# EE209_Schematic_SMT.net
KiCad netlist of a schematic drawn in Altium Designer
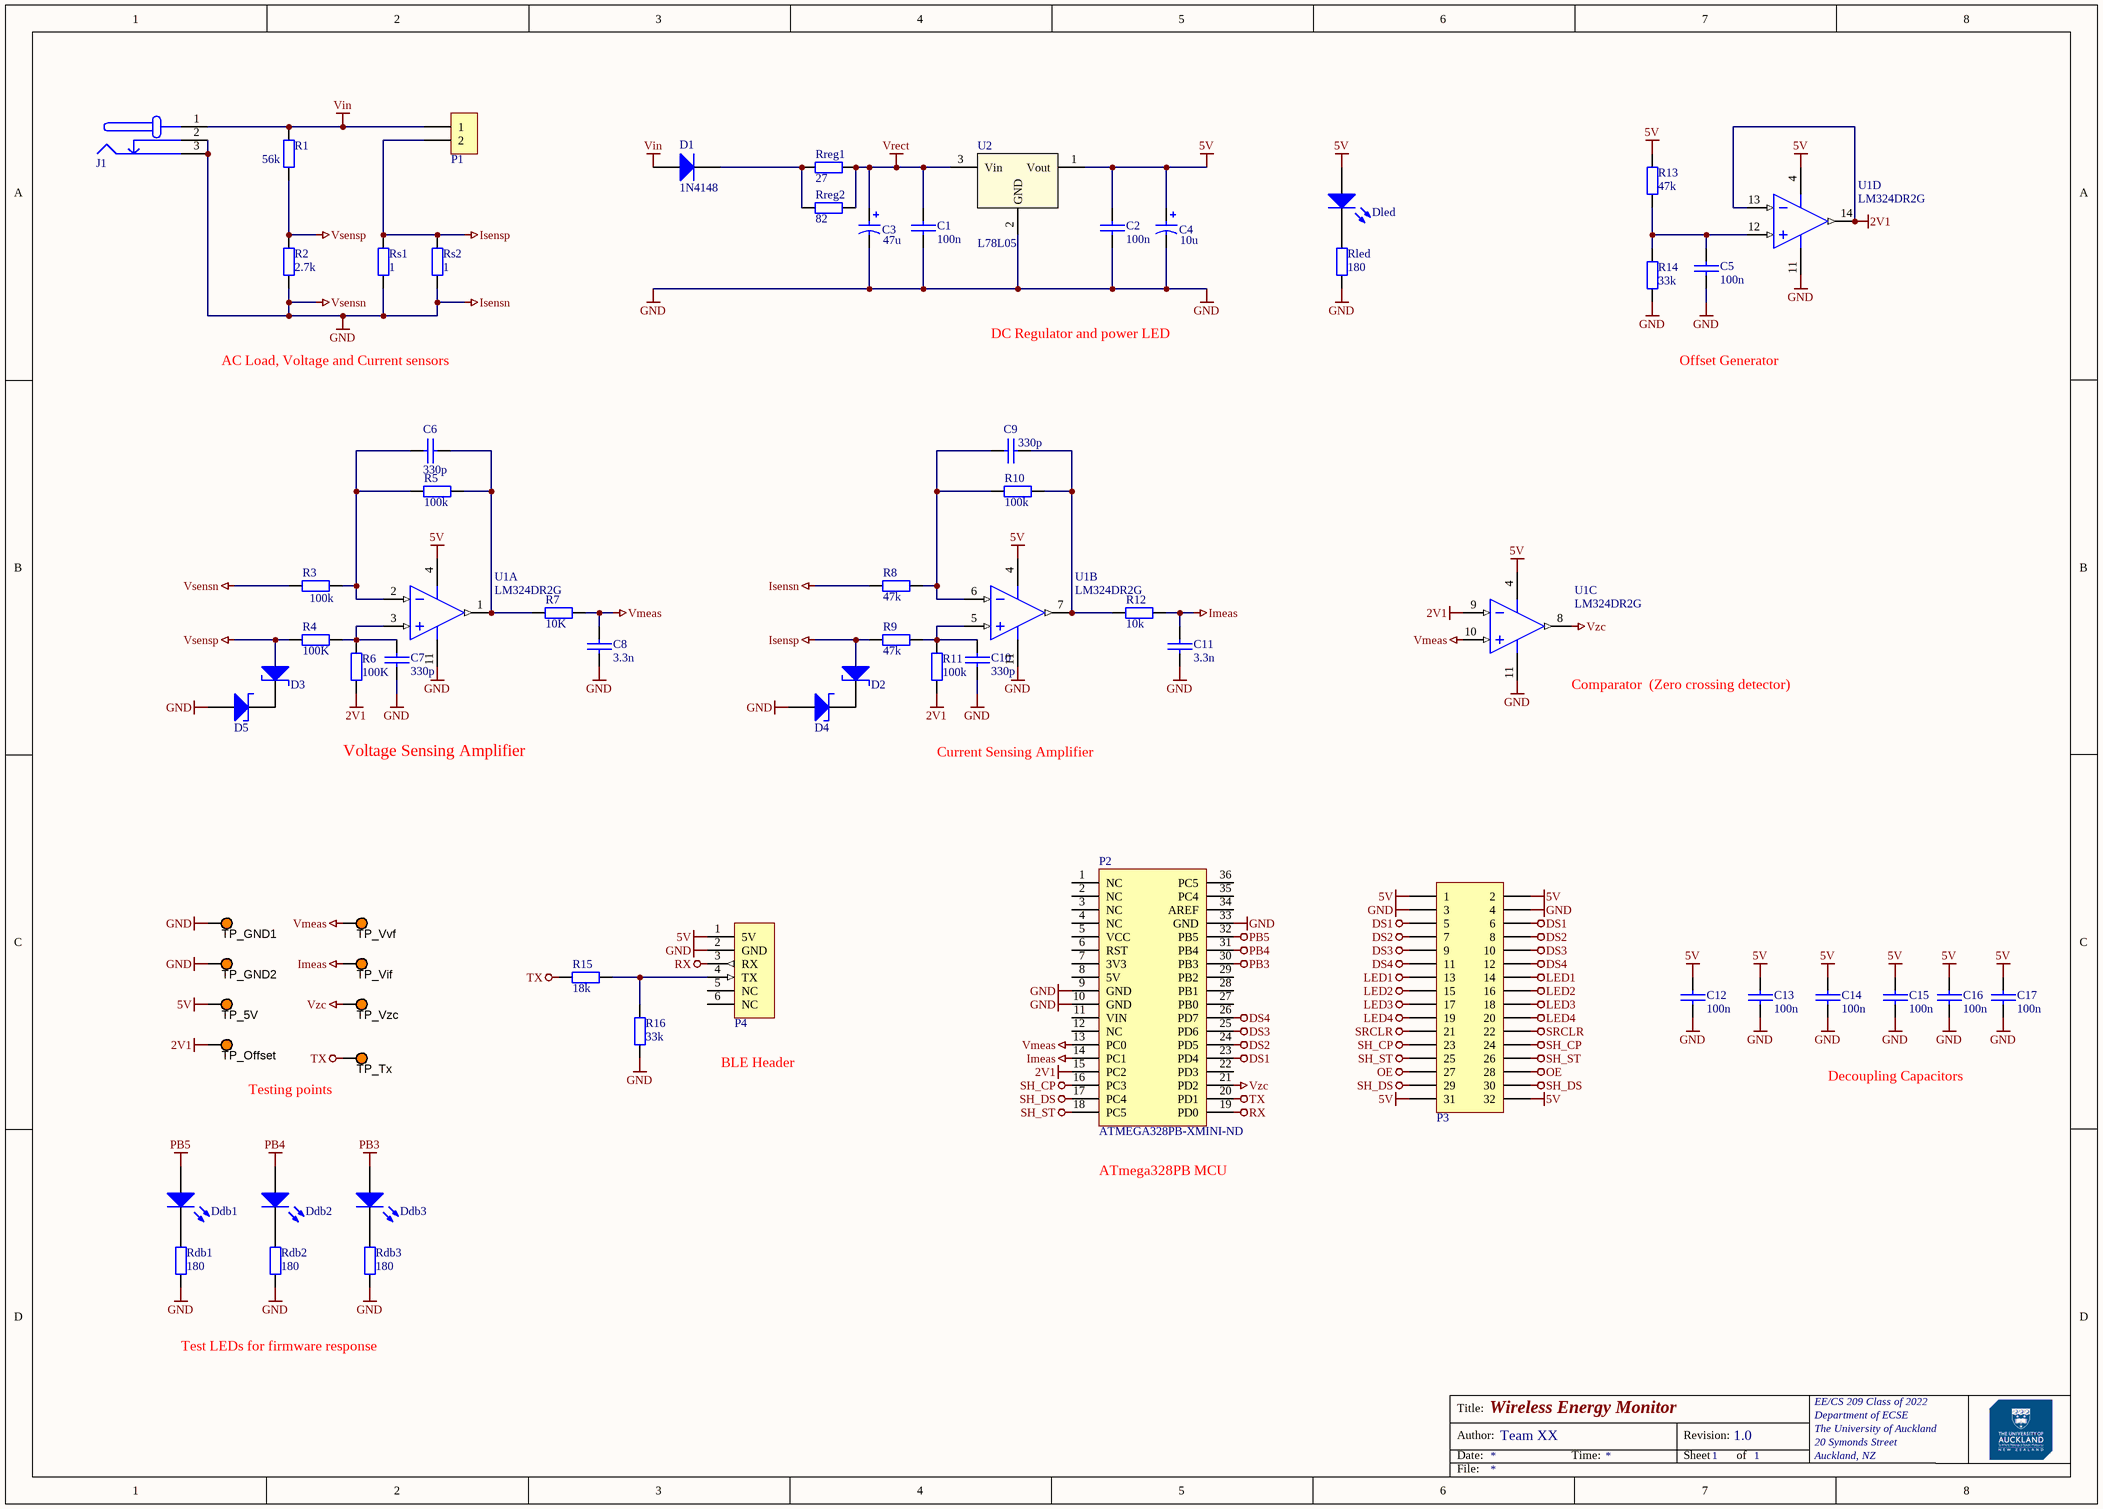
[diagram p0: EE209_Schematic_SMT.SchDoc]

(export (version "E")
  (design (tool "Eeschema 10.0.6"))
  (components
    (comp (ref "C1")
      (value "100n")
      (footprint "0805 CAP")
      (description "SMT ceramic capacitor 0805 size")
      (libsource (lib "EE209_Library") (part "CerCap_SMT_0805"))
    )
    (comp (ref "C2")
      (value "100n")
      (footprint "0805 CAP")
      (description "SMT ceramic capacitor 0805 size")
      (libsource (lib "EE209_Library") (part "CerCap_SMT_0805"))
    )
    (comp (ref "C3")
      (value "47u")
      (footprint "CAP POL 8x5.4mm SMT")
      (description "CAP ALUM 22UF 20% 50V SMD (Model: UWX1H220MCL1GB)")
      (fields
        (field (name "MANUFACTURER") "Nichicon")
        (field (name "MANUFACTURER PART NUMBER") "UWX1V220MCL1GB")
      )
      (libsource (lib "EE209_Library") (part "ElecCap_SMT_8D0"))
    )
    (comp (ref "C4")
      (value "10u")
      (footprint "CAP POL 8x5.4mm SMT")
      (description "CAP ALUM 22UF 20% 50V SMD (Model: UWX1H220MCL1GB)")
      (fields
        (field (name "MANUFACTURER") "Nichicon")
        (field (name "MANUFACTURER PART NUMBER") "UWX1V220MCL1GB")
      )
      (libsource (lib "EE209_Library") (part "ElecCap_SMT_8D0"))
    )
    (comp (ref "C5")
      (value "100n")
      (footprint "0805 CAP")
      (description "SMT ceramic capacitor 0805 size")
      (libsource (lib "EE209_Library") (part "CerCap_SMT_0805"))
    )
    (comp (ref "C6")
      (value "330p")
      (footprint "0805 CAP")
      (description "SMT ceramic capacitor 0805 size")
      (libsource (lib "EE209_Library") (part "CerCap_SMT_0805"))
    )
    (comp (ref "C7")
      (value "330p")
      (footprint "0805 CAP")
      (description "SMT ceramic capacitor 0805 size")
      (libsource (lib "EE209_Library") (part "CerCap_SMT_0805"))
    )
    (comp (ref "C8")
      (value "3.3n")
      (footprint "0805 CAP")
      (description "SMT ceramic capacitor 0805 size")
      (libsource (lib "EE209_Library") (part "CerCap_SMT_0805"))
    )
    (comp (ref "C9")
      (value "330p")
      (footprint "0805 CAP")
      (description "SMT ceramic capacitor 0805 size")
      (libsource (lib "EE209_Library") (part "CerCap_SMT_0805"))
    )
    (comp (ref "C10")
      (value "330p")
      (footprint "0805 CAP")
      (description "SMT ceramic capacitor 0805 size")
      (libsource (lib "EE209_Library") (part "CerCap_SMT_0805"))
    )
    (comp (ref "C11")
      (value "3.3n")
      (footprint "0805 CAP")
      (description "SMT ceramic capacitor 0805 size")
      (libsource (lib "EE209_Library") (part "CerCap_SMT_0805"))
    )
    (comp (ref "C12")
      (value "100n")
      (footprint "0805 CAP")
      (description "SMT ceramic capacitor 0805 size")
      (libsource (lib "EE209_Library") (part "CerCap_SMT_0805"))
    )
    (comp (ref "C13")
      (value "100n")
      (footprint "0805 CAP")
      (description "SMT ceramic capacitor 0805 size")
      (libsource (lib "EE209_Library") (part "CerCap_SMT_0805"))
    )
    (comp (ref "C14")
      (value "100n")
      (footprint "0805 CAP")
      (description "SMT ceramic capacitor 0805 size")
      (libsource (lib "EE209_Library") (part "CerCap_SMT_0805"))
    )
    (comp (ref "C15")
      (value "100n")
      (footprint "0805 CAP")
      (description "SMT ceramic capacitor 0805 size")
      (libsource (lib "EE209_Library") (part "CerCap_SMT_0805"))
    )
    (comp (ref "C16")
      (value "100n")
      (footprint "0805 CAP")
      (description "SMT ceramic capacitor 0805 size")
      (libsource (lib "EE209_Library") (part "CerCap_SMT_0805"))
    )
    (comp (ref "C17")
      (value "100n")
      (footprint "0805 CAP")
      (description "SMT ceramic capacitor 0805 size")
      (libsource (lib "EE209_Library") (part "CerCap_SMT_0805"))
    )
    (comp (ref "D1")
      (value "1N4148")
      (footprint "DO214-MFG")
      (description "1N4148 100V 200mA SOD-123 diode")
      (fields
        (field (name "MANUFACTURER") "ON Semiconductor")
        (field (name "MANUFACTURER PART NUMBER") "1N4148TR")
      )
      (libsource (lib "EE209_Library") (part "ES1H_SMT_DO214"))
    )
    (comp (ref "D2")
      (value "BZT52H-B4V7")
      (footprint "SOD123")
      (description "SMT zener diode with SOD123 package")
      (fields
        (field (name "MANUFACTURER") "Nexperia USA Inc.")
        (field (name "MANUFACTURER PART NUMBER") "BZT52H-B4V7,115")
      )
      (libsource (lib "EE209_Library") (part "Zener_SMT_SOD123"))
    )
    (comp (ref "D3")
      (value "BZT52H-B4V7")
      (footprint "SOD123")
      (description "SMT zener diode with SOD123 package")
      (fields
        (field (name "MANUFACTURER") "Nexperia USA Inc.")
        (field (name "MANUFACTURER PART NUMBER") "BZT52H-B4V7,115")
      )
      (libsource (lib "EE209_Library") (part "Zener_SMT_SOD123"))
    )
    (comp (ref "D4")
      (value "BZT52H-B4V7")
      (footprint "SOD123")
      (description "SMT zener diode with SOD123 package")
      (fields
        (field (name "MANUFACTURER") "Nexperia USA Inc.")
        (field (name "MANUFACTURER PART NUMBER") "BZT52H-B4V7,115")
      )
      (libsource (lib "EE209_Library") (part "Zener_SMT_SOD123"))
    )
    (comp (ref "D5")
      (value "BZT52H-B4V7")
      (footprint "SOD123")
      (description "SMT zener diode with SOD123 package")
      (fields
        (field (name "MANUFACTURER") "Nexperia USA Inc.")
        (field (name "MANUFACTURER PART NUMBER") "BZT52H-B4V7,115")
      )
      (libsource (lib "EE209_Library") (part "Zener_SMT_SOD123"))
    )
    (comp (ref "Ddb1")
      (value "LTST-C170KGKT")
      (footprint "0805 LED")
      (description "SMT LED 0805 size")
      (fields (field (name "MANUFACTURER") "Lite-On Inc."))
      (libsource (lib "EE209_Library") (part "LED_SMT_0805"))
    )
    (comp (ref "Ddb2")
      (value "LTST-C170KGKT")
      (footprint "0805 LED")
      (description "SMT LED 0805 size")
      (fields (field (name "MANUFACTURER") "Lite-On Inc."))
      (libsource (lib "EE209_Library") (part "LED_SMT_0805"))
    )
    (comp (ref "Ddb3")
      (value "LTST-C170KGKT")
      (footprint "0805 LED")
      (description "SMT LED 0805 size")
      (fields (field (name "MANUFACTURER") "Lite-On Inc."))
      (libsource (lib "EE209_Library") (part "LED_SMT_0805"))
    )
    (comp (ref "Dled")
      (value "LTST-C170KGKT")
      (footprint "0805 LED")
      (description "SMT LED 0805 size")
      (fields (field (name "MANUFACTURER") "Lite-On Inc."))
      (libsource (lib "EE209_Library") (part "LED_SMT_0805"))
    )
    (comp (ref "J1")
      (value "DC barrel jack")
      (footprint "AC-Socket")
      (description "DC barrel jack connection to AC source")
      (libsource (lib "EE209_Library") (part "AC_Input"))
    )
    (comp (ref "P1")
      (value "Dual Banana Plugs")
      (footprint "Dual Banana Plug")
      (description "Dual banana plugs connection to the AC load")
      (fields (field (name "PUBLISHER") "Altium Limited"))
      (libsource (lib "EE209_Library") (part "AC_Output"))
    )
    (comp (ref "P2")
      (value "ATmega328PB Xplained Mini Header")
      (footprint "ATmeg328P Xplained")
      (description "Dual 18-pin headers connecting to ATmega328PB Xplained Mini")
      (fields
        (field (name "MANUFACTURER") "Microchip Technology")
        (field (name "MANUFACTURER PART NUMBER") "ATMEGA328PB-XMINI")
        (field (name "SUPPLIER PART NUMBER 1") "ATMEGA328PB-XMINI-ND")
      )
      (libsource (lib "EE209_Library") (part "ATmega328PBXplained_TH"))
    )
    (comp (ref "P3")
      (value "Display")
      (footprint "Display")
      (description "16-Pin Header Connecting Display")
      (libsource (lib "EE209_Library") (part "Display"))
    )
    (comp (ref "P4")
      (value "BLE Module Header")
      (footprint "HM10_HDR1X6")
      (description "2.54mm pitch 6-pin header for BLE module")
      (fields (field (name "PUBLISHER") "Altium Limited"))
      (libsource (lib "EE209_Library") (part "BLEModule_TH"))
    )
    (comp (ref "R1")
      (value "56k")
      (footprint "0805 RES")
      (description "0805 resistor")
      (fields (field (name "PUBLISHER") "Altium Limited"))
      (libsource (lib "EE209_Library") (part "Res_SMT_0805"))
    )
    (comp (ref "R2")
      (value "2.7k")
      (footprint "0805 RES")
      (description "0805 resistor")
      (fields (field (name "PUBLISHER") "Altium Limited"))
      (libsource (lib "EE209_Library") (part "Res_SMT_0805"))
    )
    (comp (ref "R3")
      (value "100k")
      (footprint "0805 RES")
      (description "0805 resistor")
      (fields (field (name "PUBLISHER") "Altium Limited"))
      (libsource (lib "") (part "Res_SMT_0805_1"))
    )
    (comp (ref "R4")
      (value "100K")
      (footprint "0805 RES")
      (description "0805 resistor")
      (fields (field (name "PUBLISHER") "Altium Limited"))
      (libsource (lib "") (part "Res_SMT_0805_1"))
    )
    (comp (ref "R5")
      (value "100k")
      (footprint "0805 RES")
      (description "0805 resistor")
      (fields (field (name "PUBLISHER") "Altium Limited"))
      (libsource (lib "") (part "Res_SMT_0805_2"))
    )
    (comp (ref "R6")
      (value "100K")
      (footprint "0805 RES")
      (description "0805 resistor")
      (fields (field (name "PUBLISHER") "Altium Limited"))
      (libsource (lib "") (part "Res_SMT_0805_3"))
    )
    (comp (ref "R7")
      (value "10K")
      (footprint "0805 RES")
      (description "0805 resistor")
      (fields (field (name "PUBLISHER") "Altium Limited"))
      (libsource (lib "") (part "Res_SMT_0805_1"))
    )
    (comp (ref "R8")
      (value "47k")
      (footprint "0805 RES")
      (description "0805 resistor")
      (fields (field (name "PUBLISHER") "Altium Limited"))
      (libsource (lib "") (part "Res_SMT_0805_1"))
    )
    (comp (ref "R9")
      (value "47k")
      (footprint "0805 RES")
      (description "0805 resistor")
      (fields (field (name "PUBLISHER") "Altium Limited"))
      (libsource (lib "") (part "Res_SMT_0805_1"))
    )
    (comp (ref "R10")
      (value "100k")
      (footprint "0805 RES")
      (description "0805 resistor")
      (fields (field (name "PUBLISHER") "Altium Limited"))
      (libsource (lib "") (part "Res_SMT_0805_2"))
    )
    (comp (ref "R11")
      (value "100k")
      (footprint "0805 RES")
      (description "0805 resistor")
      (fields (field (name "PUBLISHER") "Altium Limited"))
      (libsource (lib "") (part "Res_SMT_0805_3"))
    )
    (comp (ref "R12")
      (value "10k")
      (footprint "0805 RES")
      (description "0805 resistor")
      (fields (field (name "PUBLISHER") "Altium Limited"))
      (libsource (lib "") (part "Res_SMT_0805_1"))
    )
    (comp (ref "R13")
      (value "47k")
      (footprint "0805 RES")
      (description "0805 resistor")
      (fields (field (name "PUBLISHER") "Altium Limited"))
      (libsource (lib "EE209_Library") (part "Res_SMT_0805"))
    )
    (comp (ref "R14")
      (value "33k")
      (footprint "0805 RES")
      (description "0805 resistor")
      (fields (field (name "PUBLISHER") "Altium Limited"))
      (libsource (lib "EE209_Library") (part "Res_SMT_0805"))
    )
    (comp (ref "R15")
      (value "18k")
      (footprint "0805 RES")
      (description "0805 resistor")
      (fields (field (name "PUBLISHER") "Altium Limited"))
      (libsource (lib "") (part "Res_SMT_0805_1"))
    )
    (comp (ref "R16")
      (value "33k")
      (footprint "0805 RES")
      (description "0805 resistor")
      (fields (field (name "PUBLISHER") "Altium Limited"))
      (libsource (lib "EE209_Library") (part "Res_SMT_0805"))
    )
    (comp (ref "Rdb1")
      (value "180")
      (footprint "0805 RES")
      (description "0805 resistor")
      (fields (field (name "PUBLISHER") "Altium Limited"))
      (libsource (lib "") (part "Res_SMT_0805_3"))
    )
    (comp (ref "Rdb2")
      (value "180")
      (footprint "0805 RES")
      (description "0805 resistor")
      (fields (field (name "PUBLISHER") "Altium Limited"))
      (libsource (lib "") (part "Res_SMT_0805_3"))
    )
    (comp (ref "Rdb3")
      (value "180")
      (footprint "0805 RES")
      (description "0805 resistor")
      (fields (field (name "PUBLISHER") "Altium Limited"))
      (libsource (lib "") (part "Res_SMT_0805_3"))
    )
    (comp (ref "Rled")
      (value "180")
      (footprint "0805 RES")
      (description "0805 resistor")
      (fields (field (name "PUBLISHER") "Altium Limited"))
      (libsource (lib "EE209_Library") (part "Res_SMT_0805"))
    )
    (comp (ref "Rreg1")
      (value "27")
      (footprint "0805 RES")
      (description "0805 resistor")
      (fields (field (name "PUBLISHER") "Altium Limited"))
      (libsource (lib "") (part "Res_SMT_0805_1"))
    )
    (comp (ref "Rreg2")
      (value "82")
      (footprint "0805 RES")
      (description "0805 resistor")
      (fields (field (name "PUBLISHER") "Altium Limited"))
      (libsource (lib "") (part "Res_SMT_0805_1"))
    )
    (comp (ref "Rs1")
      (value "1")
      (footprint "0805 RES")
      (description "0805 resistor")
      (fields (field (name "PUBLISHER") "Altium Limited"))
      (libsource (lib "EE209_Library") (part "Res_SMT_0805"))
    )
    (comp (ref "Rs2")
      (value "1")
      (footprint "0805 RES")
      (description "0805 resistor")
      (fields (field (name "PUBLISHER") "Altium Limited"))
      (libsource (lib "EE209_Library") (part "Res_SMT_0805"))
    )
    (comp (ref "TP_5V")
      (value "5003")
      (footprint "TP_TH")
      (description "Test Point, Orange, 1-Pin THD, RoHS")
      (libsource (lib "EE209_Library") (part "TestPoint"))
    )
    (comp (ref "TP_GND1")
      (value "5003")
      (footprint "TP_TH")
      (description "Test Point, Orange, 1-Pin THD, RoHS")
      (libsource (lib "EE209_Library") (part "TestPoint"))
    )
    (comp (ref "TP_GND2")
      (value "5003")
      (footprint "TP_TH")
      (description "Test Point, Orange, 1-Pin THD, RoHS")
      (libsource (lib "EE209_Library") (part "TestPoint"))
    )
    (comp (ref "TP_Offset")
      (value "5003")
      (footprint "TP_TH")
      (description "Test Point, Orange, 1-Pin THD, RoHS")
      (libsource (lib "EE209_Library") (part "TestPoint"))
    )
    (comp (ref "TP_Tx")
      (value "5003")
      (footprint "TP_TH")
      (description "Test Point, Orange, 1-Pin THD, RoHS")
      (libsource (lib "EE209_Library") (part "TestPoint"))
    )
    (comp (ref "TP_Vif")
      (value "5003")
      (footprint "TP_TH")
      (description "Test Point, Orange, 1-Pin THD, RoHS")
      (libsource (lib "EE209_Library") (part "TestPoint"))
    )
    (comp (ref "TP_Vvf")
      (value "5003")
      (footprint "TP_TH")
      (description "Test Point, Orange, 1-Pin THD, RoHS")
      (libsource (lib "EE209_Library") (part "TestPoint"))
    )
    (comp (ref "TP_Vzc")
      (value "5003")
      (footprint "TP_TH")
      (description "Test Point, Orange, 1-Pin THD, RoHS")
      (libsource (lib "EE209_Library") (part "TestPoint"))
    )
    (comp (ref "U1")
      (value "LM324DR2G")
      (footprint "SOIC-14")
      (fields (field (name "MANUFACTURER") "On Semiconductor"))
      (libsource (lib "EE209_Library") (part "LM324DR_SMT_SOIC16"))
    )
    (comp (ref "U2")
      (value "L78L05")
      (footprint "SOT-89")
      (description "LDO Voltage Regulator 5V")
      (libsource (lib "EE209_Library") (part "L78L05_SMT_SOT89"))
    )
  )
  (nets
    (net (code "1") (name "2V1") (class "Default")
      (node (ref "P2") (pin "15") (pinfunction "PC2_15") (pintype "passive"))
      (node (ref "R11") (pin "2") (pinfunction "2_2") (pintype "passive"))
      (node (ref "R6") (pin "2") (pinfunction "2_2") (pintype "passive"))
      (node (ref "TP_Offset") (pin "1") (pinfunction "1_1") (pintype "passive"))
      (node (ref "U1") (pin "13") (pinfunction "IN4-_13") (pintype "input"))
      (node (ref "U1") (pin "14") (pinfunction "OUT4_14") (pintype "output"))
      (node (ref "U1") (pin "9") (pinfunction "IN3-_9") (pintype "input"))
    )
    (net (code "2") (name "5V") (class "Default")
      (node (ref "C12") (pin "1") (pinfunction "1_1") (pintype "passive"))
      (node (ref "C13") (pin "1") (pinfunction "1_1") (pintype "passive"))
      (node (ref "C14") (pin "1") (pinfunction "1_1") (pintype "passive"))
      (node (ref "C15") (pin "1") (pinfunction "1_1") (pintype "passive"))
      (node (ref "C16") (pin "1") (pinfunction "1_1") (pintype "passive"))
      (node (ref "C17") (pin "1") (pinfunction "1_1") (pintype "passive"))
      (node (ref "C2") (pin "1") (pinfunction "1_1") (pintype "passive"))
      (node (ref "C4") (pin "1") (pinfunction "1_1") (pintype "passive"))
      (node (ref "Dled") (pin "1") (pinfunction "A_1") (pintype "passive"))
      (node (ref "P3") (pin "1") (pinfunction "1_1") (pintype "passive"))
      (node (ref "P3") (pin "2") (pinfunction "2_2") (pintype "passive"))
      (node (ref "P3") (pin "31") (pinfunction "31_31") (pintype "passive"))
      (node (ref "P3") (pin "32") (pinfunction "32_32") (pintype "passive"))
      (node (ref "P4") (pin "1") (pinfunction "5V_1") (pintype "passive"))
      (node (ref "R13") (pin "2") (pinfunction "2_2") (pintype "passive"))
      (node (ref "TP_5V") (pin "1") (pinfunction "1_1") (pintype "passive"))
      (node (ref "U1") (pin "4") (pinfunction "VCC_4") (pintype "power_in"))
      (node (ref "U2") (pin "1") (pinfunction "Vout_1") (pintype "passive"))
    )
    (net (code "3") (name "DS1") (class "Default")
      (node (ref "P2") (pin "23") (pinfunction "PD4_23") (pintype "passive"))
      (node (ref "P3") (pin "5") (pinfunction "5_5") (pintype "passive"))
      (node (ref "P3") (pin "6") (pinfunction "6_6") (pintype "passive"))
    )
    (net (code "4") (name "DS2") (class "Default")
      (node (ref "P2") (pin "24") (pinfunction "PD5_24") (pintype "passive"))
      (node (ref "P3") (pin "7") (pinfunction "7_7") (pintype "passive"))
      (node (ref "P3") (pin "8") (pinfunction "8_8") (pintype "passive"))
    )
    (net (code "5") (name "DS3") (class "Default")
      (node (ref "P2") (pin "25") (pinfunction "PD6_25") (pintype "passive"))
      (node (ref "P3") (pin "10") (pinfunction "10_10") (pintype "passive"))
      (node (ref "P3") (pin "9") (pinfunction "9_9") (pintype "passive"))
    )
    (net (code "6") (name "DS4") (class "Default")
      (node (ref "P2") (pin "26") (pinfunction "PD7_26") (pintype "passive"))
      (node (ref "P3") (pin "11") (pinfunction "11_11") (pintype "passive"))
      (node (ref "P3") (pin "12") (pinfunction "12_12") (pintype "passive"))
    )
    (net (code "7") (name "GND") (class "Default")
      (node (ref "C1") (pin "2") (pinfunction "2_2") (pintype "passive"))
      (node (ref "C10") (pin "2") (pinfunction "2_2") (pintype "passive"))
      (node (ref "C11") (pin "2") (pinfunction "2_2") (pintype "passive"))
      (node (ref "C12") (pin "2") (pinfunction "2_2") (pintype "passive"))
      (node (ref "C13") (pin "2") (pinfunction "2_2") (pintype "passive"))
      (node (ref "C14") (pin "2") (pinfunction "2_2") (pintype "passive"))
      (node (ref "C15") (pin "2") (pinfunction "2_2") (pintype "passive"))
      (node (ref "C16") (pin "2") (pinfunction "2_2") (pintype "passive"))
      (node (ref "C17") (pin "2") (pinfunction "2_2") (pintype "passive"))
      (node (ref "C2") (pin "2") (pinfunction "2_2") (pintype "passive"))
      (node (ref "C3") (pin "2") (pinfunction "2_2") (pintype "passive"))
      (node (ref "C4") (pin "2") (pinfunction "2_2") (pintype "passive"))
      (node (ref "C5") (pin "2") (pinfunction "2_2") (pintype "passive"))
      (node (ref "C7") (pin "2") (pinfunction "2_2") (pintype "passive"))
      (node (ref "C8") (pin "2") (pinfunction "2_2") (pintype "passive"))
      (node (ref "D4") (pin "1") (pinfunction "A_1") (pintype "passive"))
      (node (ref "D5") (pin "1") (pinfunction "A_1") (pintype "passive"))
      (node (ref "J1") (pin "2") (pinfunction "GND_ALT_2") (pintype "power_in"))
      (node (ref "J1") (pin "3") (pinfunction "GND_3") (pintype "power_in"))
      (node (ref "P2") (pin "10") (pinfunction "GND_10") (pintype "power_in"))
      (node (ref "P2") (pin "33") (pinfunction "GND_33") (pintype "passive"))
      (node (ref "P2") (pin "9") (pinfunction "GND_9") (pintype "power_in"))
      (node (ref "P3") (pin "3") (pinfunction "3_3") (pintype "passive"))
      (node (ref "P3") (pin "4") (pinfunction "4_4") (pintype "passive"))
      (node (ref "P4") (pin "2") (pinfunction "GND_2") (pintype "passive"))
      (node (ref "R14") (pin "1") (pinfunction "1_1") (pintype "passive"))
      (node (ref "R16") (pin "1") (pinfunction "1_1") (pintype "passive"))
      (node (ref "R2") (pin "1") (pinfunction "1_1") (pintype "passive"))
      (node (ref "R3") (pin "1") (pinfunction "1_1") (pintype "passive"))
      (node (ref "R8") (pin "1") (pinfunction "1_1") (pintype "passive"))
      (node (ref "Rdb1") (pin "2") (pinfunction "2_2") (pintype "passive"))
      (node (ref "Rdb2") (pin "2") (pinfunction "2_2") (pintype "passive"))
      (node (ref "Rdb3") (pin "2") (pinfunction "2_2") (pintype "passive"))
      (node (ref "Rled") (pin "1") (pinfunction "1_1") (pintype "passive"))
      (node (ref "Rs1") (pin "1") (pinfunction "1_1") (pintype "passive"))
      (node (ref "Rs2") (pin "1") (pinfunction "1_1") (pintype "passive"))
      (node (ref "TP_GND1") (pin "1") (pinfunction "1_1") (pintype "passive"))
      (node (ref "TP_GND2") (pin "1") (pinfunction "1_1") (pintype "passive"))
      (node (ref "U1") (pin "11") (pinfunction "VEE/GND_11") (pintype "power_in"))
      (node (ref "U2") (pin "2") (pinfunction "GND_2") (pintype "passive"))
    )
    (net (code "8") (name "Imeas") (class "Default")
      (node (ref "C11") (pin "1") (pinfunction "1_1") (pintype "passive"))
      (node (ref "P2") (pin "14") (pinfunction "PC1_14") (pintype "passive"))
      (node (ref "R12") (pin "2") (pinfunction "2_2") (pintype "passive"))
      (node (ref "TP_Vif") (pin "1") (pinfunction "1_1") (pintype "passive"))
    )
    (net (code "9") (name "Isensp") (class "Default")
      (node (ref "D2") (pin "1") (pinfunction "A_1") (pintype "passive"))
      (node (ref "P1") (pin "2") (pinfunction "2_2") (pintype "passive"))
      (node (ref "R9") (pin "1") (pinfunction "1_1") (pintype "passive"))
      (node (ref "Rs1") (pin "2") (pinfunction "2_2") (pintype "passive"))
      (node (ref "Rs2") (pin "2") (pinfunction "2_2") (pintype "passive"))
    )
    (net (code "10") (name "LED1") (class "Default")
      (node (ref "P3") (pin "13") (pinfunction "13_13") (pintype "passive"))
      (node (ref "P3") (pin "14") (pinfunction "14_14") (pintype "passive"))
    )
    (net (code "11") (name "LED2") (class "Default")
      (node (ref "P3") (pin "15") (pinfunction "15_15") (pintype "passive"))
      (node (ref "P3") (pin "16") (pinfunction "16_16") (pintype "passive"))
    )
    (net (code "12") (name "LED3") (class "Default")
      (node (ref "P3") (pin "17") (pinfunction "17_17") (pintype "passive"))
      (node (ref "P3") (pin "18") (pinfunction "18_18") (pintype "passive"))
    )
    (net (code "13") (name "LED4") (class "Default")
      (node (ref "P3") (pin "19") (pinfunction "19_19") (pintype "passive"))
      (node (ref "P3") (pin "20") (pinfunction "20_20") (pintype "passive"))
    )
    (net (code "14") (name "Net-(D1-K)") (class "Default")
      (node (ref "D1") (pin "2") (pinfunction "K_2") (pintype "passive"))
      (node (ref "Rreg1") (pin "1") (pinfunction "1_1") (pintype "passive"))
      (node (ref "Rreg2") (pin "1") (pinfunction "1_1") (pintype "passive"))
    )
    (net (code "15") (name "Net-(D2-K)") (class "Default")
      (node (ref "D2") (pin "2") (pinfunction "K_2") (pintype "passive"))
      (node (ref "D4") (pin "2") (pinfunction "K_2") (pintype "passive"))
    )
    (net (code "16") (name "Net-(D3-K)") (class "Default")
      (node (ref "D3") (pin "2") (pinfunction "K_2") (pintype "passive"))
      (node (ref "D5") (pin "2") (pinfunction "K_2") (pintype "passive"))
    )
    (net (code "17") (name "Net-(Ddb1-K)") (class "Default")
      (node (ref "Ddb1") (pin "2") (pinfunction "K_2") (pintype "passive"))
      (node (ref "Rdb1") (pin "1") (pinfunction "1_1") (pintype "passive"))
    )
    (net (code "18") (name "Net-(Ddb2-K)") (class "Default")
      (node (ref "Ddb2") (pin "2") (pinfunction "K_2") (pintype "passive"))
      (node (ref "Rdb2") (pin "1") (pinfunction "1_1") (pintype "passive"))
    )
    (net (code "19") (name "Net-(Ddb3-K)") (class "Default")
      (node (ref "Ddb3") (pin "2") (pinfunction "K_2") (pintype "passive"))
      (node (ref "Rdb3") (pin "1") (pinfunction "1_1") (pintype "passive"))
    )
    (net (code "20") (name "Net-(Dled-K)") (class "Default")
      (node (ref "Dled") (pin "2") (pinfunction "K_2") (pintype "passive"))
      (node (ref "Rled") (pin "2") (pinfunction "2_2") (pintype "passive"))
    )
    (net (code "21") (name "Net-(P4-TX)") (class "Default")
      (node (ref "P4") (pin "4") (pinfunction "TX_4") (pintype "input"))
      (node (ref "R15") (pin "2") (pinfunction "2_2") (pintype "passive"))
      (node (ref "R16") (pin "2") (pinfunction "2_2") (pintype "passive"))
    )
    (net (code "22") (name "Net-(U1A-IN1+)") (class "Default")
      (node (ref "C7") (pin "1") (pinfunction "1_1") (pintype "passive"))
      (node (ref "R4") (pin "2") (pinfunction "2_2") (pintype "passive"))
      (node (ref "R6") (pin "1") (pinfunction "1_1") (pintype "passive"))
      (node (ref "U1") (pin "3") (pinfunction "IN1+_3") (pintype "input"))
    )
    (net (code "23") (name "Net-(U1A-IN1-)") (class "Default")
      (node (ref "C6") (pin "1") (pinfunction "1_1") (pintype "passive"))
      (node (ref "R3") (pin "2") (pinfunction "2_2") (pintype "passive"))
      (node (ref "R5") (pin "2") (pinfunction "2_2") (pintype "passive"))
      (node (ref "U1") (pin "2") (pinfunction "IN1-_2") (pintype "input"))
    )
    (net (code "24") (name "Net-(U1A-OUT1)") (class "Default")
      (node (ref "C6") (pin "2") (pinfunction "2_2") (pintype "passive"))
      (node (ref "R5") (pin "1") (pinfunction "1_1") (pintype "passive"))
      (node (ref "R7") (pin "1") (pinfunction "1_1") (pintype "passive"))
      (node (ref "U1") (pin "1") (pinfunction "OUT1_1") (pintype "output"))
    )
    (net (code "25") (name "Net-(U1B-IN2+)") (class "Default")
      (node (ref "C10") (pin "1") (pinfunction "1_1") (pintype "passive"))
      (node (ref "R11") (pin "1") (pinfunction "1_1") (pintype "passive"))
      (node (ref "R9") (pin "2") (pinfunction "2_2") (pintype "passive"))
      (node (ref "U1") (pin "5") (pinfunction "IN2+_5") (pintype "input"))
    )
    (net (code "26") (name "Net-(U1B-IN2-)") (class "Default")
      (node (ref "C9") (pin "1") (pinfunction "1_1") (pintype "passive"))
      (node (ref "R10") (pin "2") (pinfunction "2_2") (pintype "passive"))
      (node (ref "R8") (pin "2") (pinfunction "2_2") (pintype "passive"))
      (node (ref "U1") (pin "6") (pinfunction "IN2-_6") (pintype "input"))
    )
    (net (code "27") (name "Net-(U1B-OUT2)") (class "Default")
      (node (ref "C9") (pin "2") (pinfunction "2_2") (pintype "passive"))
      (node (ref "R10") (pin "1") (pinfunction "1_1") (pintype "passive"))
      (node (ref "R12") (pin "1") (pinfunction "1_1") (pintype "passive"))
      (node (ref "U1") (pin "7") (pinfunction "OUT2_7") (pintype "output"))
    )
    (net (code "28") (name "Net-(U1D-IN4+)") (class "Default")
      (node (ref "C5") (pin "1") (pinfunction "1_1") (pintype "passive"))
      (node (ref "R13") (pin "1") (pinfunction "1_1") (pintype "passive"))
      (node (ref "R14") (pin "2") (pinfunction "2_2") (pintype "passive"))
      (node (ref "U1") (pin "12") (pinfunction "IN4+_12") (pintype "input"))
    )
    (net (code "29") (name "OE") (class "Default")
      (node (ref "P3") (pin "27") (pinfunction "27_27") (pintype "passive"))
      (node (ref "P3") (pin "28") (pinfunction "28_28") (pintype "passive"))
    )
    (net (code "30") (name "PB3") (class "Default")
      (node (ref "Ddb3") (pin "1") (pinfunction "A_1") (pintype "passive"))
      (node (ref "P2") (pin "30") (pinfunction "PB3_30") (pintype "passive"))
    )
    (net (code "31") (name "PB4") (class "Default")
      (node (ref "Ddb2") (pin "1") (pinfunction "A_1") (pintype "passive"))
      (node (ref "P2") (pin "31") (pinfunction "PB4_31") (pintype "passive"))
    )
    (net (code "32") (name "PB5") (class "Default")
      (node (ref "Ddb1") (pin "1") (pinfunction "A_1") (pintype "passive"))
      (node (ref "P2") (pin "32") (pinfunction "PB5_32") (pintype "passive"))
    )
    (net (code "33") (name "RX") (class "Default")
      (node (ref "P2") (pin "19") (pinfunction "PD0_19") (pintype "passive"))
      (node (ref "P4") (pin "3") (pinfunction "RX_3") (pintype "output"))
    )
    (net (code "34") (name "SH_CP") (class "Default")
      (node (ref "P2") (pin "16") (pinfunction "PC3_16") (pintype "passive"))
      (node (ref "P3") (pin "23") (pinfunction "23_23") (pintype "passive"))
      (node (ref "P3") (pin "24") (pinfunction "24_24") (pintype "passive"))
    )
    (net (code "35") (name "SH_DS") (class "Default")
      (node (ref "P2") (pin "17") (pinfunction "PC4_17") (pintype "passive"))
      (node (ref "P3") (pin "29") (pinfunction "29_29") (pintype "passive"))
      (node (ref "P3") (pin "30") (pinfunction "30_30") (pintype "passive"))
    )
    (net (code "36") (name "SH_ST") (class "Default")
      (node (ref "P2") (pin "18") (pinfunction "PC5_18") (pintype "passive"))
      (node (ref "P3") (pin "25") (pinfunction "25_25") (pintype "passive"))
      (node (ref "P3") (pin "26") (pinfunction "26_26") (pintype "passive"))
    )
    (net (code "37") (name "SRCLR") (class "Default")
      (node (ref "P3") (pin "21") (pinfunction "21_21") (pintype "passive"))
      (node (ref "P3") (pin "22") (pinfunction "22_22") (pintype "passive"))
    )
    (net (code "38") (name "TX") (class "Default")
      (node (ref "P2") (pin "20") (pinfunction "PD1_20") (pintype "passive"))
      (node (ref "R15") (pin "1") (pinfunction "1_1") (pintype "passive"))
      (node (ref "TP_Tx") (pin "1") (pinfunction "1_1") (pintype "passive"))
    )
    (net (code "39") (name "Vin") (class "Default")
      (node (ref "D1") (pin "1") (pinfunction "A_1") (pintype "passive"))
      (node (ref "J1") (pin "1") (pinfunction "VCC_1") (pintype "power_in"))
      (node (ref "P1") (pin "1") (pinfunction "1_1") (pintype "passive"))
      (node (ref "R1") (pin "2") (pinfunction "2_2") (pintype "passive"))
    )
    (net (code "40") (name "Vmeas") (class "Default")
      (node (ref "C8") (pin "1") (pinfunction "1_1") (pintype "passive"))
      (node (ref "P2") (pin "13") (pinfunction "PC0_13") (pintype "passive"))
      (node (ref "R7") (pin "2") (pinfunction "2_2") (pintype "passive"))
      (node (ref "TP_Vvf") (pin "1") (pinfunction "1_1") (pintype "passive"))
      (node (ref "U1") (pin "10") (pinfunction "IN3+_10") (pintype "input"))
    )
    (net (code "41") (name "Vrect") (class "Default")
      (node (ref "C1") (pin "1") (pinfunction "1_1") (pintype "passive"))
      (node (ref "C3") (pin "1") (pinfunction "1_1") (pintype "passive"))
      (node (ref "Rreg1") (pin "2") (pinfunction "2_2") (pintype "passive"))
      (node (ref "Rreg2") (pin "2") (pinfunction "2_2") (pintype "passive"))
      (node (ref "U2") (pin "3") (pinfunction "Vin_3") (pintype "passive"))
    )
    (net (code "42") (name "Vsensp") (class "Default")
      (node (ref "D3") (pin "1") (pinfunction "A_1") (pintype "passive"))
      (node (ref "R1") (pin "1") (pinfunction "1_1") (pintype "passive"))
      (node (ref "R2") (pin "2") (pinfunction "2_2") (pintype "passive"))
      (node (ref "R4") (pin "1") (pinfunction "1_1") (pintype "passive"))
    )
    (net (code "43") (name "Vzc") (class "Default")
      (node (ref "P2") (pin "21") (pinfunction "PD2_21") (pintype "passive"))
      (node (ref "TP_Vzc") (pin "1") (pinfunction "1_1") (pintype "passive"))
      (node (ref "U1") (pin "8") (pinfunction "OUT3_8") (pintype "output"))
    )
    (net (code "44") (name "unconnected-(P2-3V3-Pad7)") (class "Default")
      (node (ref "P2") (pin "7") (pinfunction "3V3_7") (pintype "passive"))
    )
    (net (code "45") (name "unconnected-(P2-5V-Pad8)") (class "Default")
      (node (ref "P2") (pin "8") (pinfunction "5V_8") (pintype "power_in"))
    )
    (net (code "46") (name "unconnected-(P2-AREF-Pad34)") (class "Default")
      (node (ref "P2") (pin "34") (pinfunction "AREF_34") (pintype "passive"))
    )
    (net (code "47") (name "unconnected-(P2-NC-Pad1)") (class "Default")
      (node (ref "P2") (pin "1") (pinfunction "NC_1") (pintype "passive"))
    )
    (net (code "48") (name "unconnected-(P2-NC-Pad2)") (class "Default")
      (node (ref "P2") (pin "2") (pinfunction "NC_2") (pintype "passive"))
    )
    (net (code "49") (name "unconnected-(P2-NC-Pad3)") (class "Default")
      (node (ref "P2") (pin "3") (pinfunction "NC_3") (pintype "passive"))
    )
    (net (code "50") (name "unconnected-(P2-NC-Pad4)") (class "Default")
      (node (ref "P2") (pin "4") (pinfunction "NC_4") (pintype "passive"))
    )
    (net (code "51") (name "unconnected-(P2-NC-Pad12)") (class "Default")
      (node (ref "P2") (pin "12") (pinfunction "NC_12") (pintype "passive"))
    )
    (net (code "52") (name "unconnected-(P2-PB0-Pad27)") (class "Default")
      (node (ref "P2") (pin "27") (pinfunction "PB0_27") (pintype "passive"))
    )
    (net (code "53") (name "unconnected-(P2-PB1-Pad28)") (class "Default")
      (node (ref "P2") (pin "28") (pinfunction "PB1_28") (pintype "passive"))
    )
    (net (code "54") (name "unconnected-(P2-PB2-Pad29)") (class "Default")
      (node (ref "P2") (pin "29") (pinfunction "PB2_29") (pintype "passive"))
    )
    (net (code "55") (name "unconnected-(P2-PC4-Pad35)") (class "Default")
      (node (ref "P2") (pin "35") (pinfunction "PC4_35") (pintype "passive"))
    )
    (net (code "56") (name "unconnected-(P2-PC5-Pad36)") (class "Default")
      (node (ref "P2") (pin "36") (pinfunction "PC5_36") (pintype "passive"))
    )
    (net (code "57") (name "unconnected-(P2-PD3-Pad22)") (class "Default")
      (node (ref "P2") (pin "22") (pinfunction "PD3_22") (pintype "passive"))
    )
    (net (code "58") (name "unconnected-(P2-RST-Pad6)") (class "Default")
      (node (ref "P2") (pin "6") (pinfunction "RST_6") (pintype "passive"))
    )
    (net (code "59") (name "unconnected-(P2-VCC-Pad5)") (class "Default")
      (node (ref "P2") (pin "5") (pinfunction "VCC_5") (pintype "power_in"))
    )
    (net (code "60") (name "unconnected-(P2-VIN-Pad11)") (class "Default")
      (node (ref "P2") (pin "11") (pinfunction "VIN_11") (pintype "power_in"))
    )
    (net (code "61") (name "unconnected-(P4-NC-Pad5)") (class "Default")
      (node (ref "P4") (pin "5") (pinfunction "NC_5") (pintype "passive"))
    )
    (net (code "62") (name "unconnected-(P4-NC-Pad6)") (class "Default")
      (node (ref "P4") (pin "6") (pinfunction "NC_6") (pintype "passive"))
    )
  )
)
